# leptonBreakoutV4.net
KiCad netlist of a schematic drawn in EAGLE
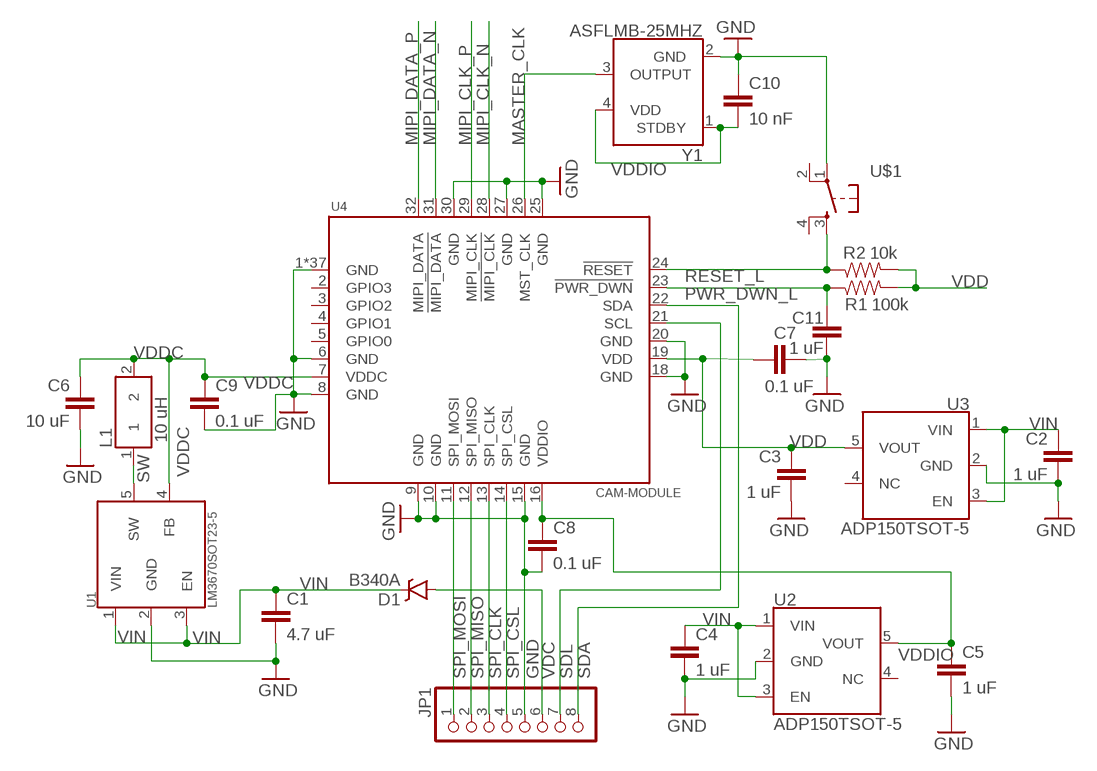
[diagram p0: schematic, sheet 1]

(export (version "E")
  (design (tool "Eeschema 10.0.6"))
  (components
    (comp (ref "C1")
      (value "4.7 uF")
      (footprint "eagle-import:0805")
      (libsource (lib "eagle-import") (part "CAP0805"))
    )
    (comp (ref "C2")
      (value "1 uF")
      (footprint "eagle-import:0805")
      (libsource (lib "eagle-import") (part "CAP0805"))
    )
    (comp (ref "C3")
      (value "1 uF")
      (footprint "eagle-import:0805")
      (libsource (lib "eagle-import") (part "CAP0805"))
    )
    (comp (ref "C4")
      (value "1 uF")
      (footprint "eagle-import:0805")
      (libsource (lib "eagle-import") (part "CAP0805"))
    )
    (comp (ref "C5")
      (value "1 uF")
      (footprint "eagle-import:0805")
      (libsource (lib "eagle-import") (part "CAP0805"))
    )
    (comp (ref "C6")
      (value "10 uF")
      (footprint "eagle-import:0805")
      (libsource (lib "eagle-import") (part "CAP0805"))
    )
    (comp (ref "C7")
      (value "0.1 uF")
      (footprint "eagle-import:0805")
      (libsource (lib "eagle-import") (part "CAP0805"))
    )
    (comp (ref "C8")
      (value "0.1 uF")
      (footprint "eagle-import:0805")
      (libsource (lib "eagle-import") (part "CAP0805"))
    )
    (comp (ref "C9")
      (value "0.1 uF")
      (footprint "eagle-import:0805")
      (libsource (lib "eagle-import") (part "CAP0805"))
    )
    (comp (ref "C10")
      (value "10 nF")
      (footprint "eagle-import:0805")
      (libsource (lib "eagle-import") (part "CAP0805"))
    )
    (comp (ref "C11")
      (value "1 uF")
      (footprint "eagle-import:0805")
      (libsource (lib "eagle-import") (part "CAP0805"))
    )
    (comp (ref "D1")
      (value "B340A")
      (footprint "eagle-import:SMA-DIODE")
      (libsource (lib "eagle-import") (part "DIODE-SCHOTTKY-B340A"))
    )
    (comp (ref "JP1")
      (value "PINHD-1X8/90")
      (footprint "eagle-import:1X08_90")
      (libsource (lib "eagle-import") (part "PINHD-1X8/90"))
    )
    (comp (ref "L1")
      (value "10 uH")
      (footprint "eagle-import:SMD-INDUCTOR")
      (libsource (lib "eagle-import") (part "SMD-INDUCTOR"))
    )
    (comp (ref "R1")
      (value "100k")
      (footprint "eagle-import:0805")
      (libsource (lib "eagle-import") (part "RESISTOR0805-RES"))
    )
    (comp (ref "R2")
      (value "10k")
      (footprint "eagle-import:0805")
      (libsource (lib "eagle-import") (part "RESISTOR0805-RES"))
    )
    (comp (ref "U$1")
      (value "TACTILE-SWITCH-7914G")
      (footprint "eagle-import:7914G")
      (libsource (lib "eagle-import") (part "TACTILE-SWITCH-7914G"))
    )
    (comp (ref "U1")
      (value "LM3670SOT23-5")
      (footprint "eagle-import:SOT23-5")
      (libsource (lib "eagle-import") (part "LM3670SOT23-5"))
    )
    (comp (ref "U2")
      (value "ADP150TSOT-5")
      (footprint "eagle-import:SOT23-5")
      (libsource (lib "eagle-import") (part "ADP150TSOT-5"))
    )
    (comp (ref "U3")
      (value "ADP150TSOT-5")
      (footprint "eagle-import:SOT23-5")
      (libsource (lib "eagle-import") (part "ADP150TSOT-5"))
    )
    (comp (ref "U4")
      (value "CAM-MODULE")
      (footprint "eagle-import:CAM-SOCKET")
      (libsource (lib "eagle-import") (part "CAM-MODULE"))
    )
    (comp (ref "Y1")
      (value "ASFLMB-25MHZ")
      (footprint "eagle-import:5X3.2-CRYSTAL-OSC")
      (libsource (lib "eagle-import") (part "ASFLMB-25MHZ"))
    )
  )
  (nets
    (net (code "1") (name "/MASTER_CLK") (class "Default")
      (node (ref "U4") (pin "26") (pinfunction "MST_CLK_26") (pintype "bidirectional"))
      (node (ref "Y1") (pin "3") (pinfunction "OUTPUT_3") (pintype "bidirectional"))
    )
    (net (code "2") (name "/MIPI_CLK_N") (class "Default")
      (node (ref "U4") (pin "28") (pinfunction "~{MIPI_CLK}_28") (pintype "bidirectional"))
    )
    (net (code "3") (name "/MIPI_CLK_P") (class "Default")
      (node (ref "U4") (pin "29") (pinfunction "MIPI_CLK_29") (pintype "bidirectional"))
    )
    (net (code "4") (name "/MIPI_DATA_N") (class "Default")
      (node (ref "U4") (pin "31") (pinfunction "~{MIPI_DATA}_31") (pintype "bidirectional"))
    )
    (net (code "5") (name "/MIPI_DATA_P") (class "Default")
      (node (ref "U4") (pin "32") (pinfunction "MIPI_DATA_32") (pintype "bidirectional"))
    )
    (net (code "6") (name "/PWR_DWN_L") (class "Default")
      (node (ref "C11") (pin "1") (pinfunction "1_1") (pintype "passive"))
      (node (ref "R1") (pin "1") (pinfunction "1_1") (pintype "passive"))
      (node (ref "U4") (pin "23") (pinfunction "~{PWR_DWN}_23") (pintype "bidirectional"))
    )
    (net (code "7") (name "/RESET_L") (class "Default")
      (node (ref "R2") (pin "1") (pinfunction "1_1") (pintype "passive"))
      (node (ref "U$1") (pin "3") (pinfunction "3_3") (pintype "passive"))
      (node (ref "U4") (pin "24") (pinfunction "~{RESET}_24") (pintype "bidirectional"))
    )
    (net (code "8") (name "/SDA") (class "Default")
      (node (ref "JP1") (pin "8") (pinfunction "8_8") (pintype "passive"))
      (node (ref "U4") (pin "22") (pinfunction "SDA_22") (pintype "bidirectional"))
    )
    (net (code "9") (name "/SDL") (class "Default")
      (node (ref "JP1") (pin "7") (pinfunction "7_7") (pintype "passive"))
      (node (ref "U4") (pin "21") (pinfunction "SCL_21") (pintype "bidirectional"))
    )
    (net (code "10") (name "/SPI_CLK") (class "Default")
      (node (ref "JP1") (pin "3") (pinfunction "3_3") (pintype "passive"))
      (node (ref "U4") (pin "13") (pinfunction "SPI_CLK_13") (pintype "bidirectional"))
    )
    (net (code "11") (name "/SPI_CSL") (class "Default")
      (node (ref "JP1") (pin "4") (pinfunction "4_4") (pintype "passive"))
      (node (ref "U4") (pin "14") (pinfunction "SPI_CSL_14") (pintype "bidirectional"))
    )
    (net (code "12") (name "/SPI_MISO") (class "Default")
      (node (ref "JP1") (pin "2") (pinfunction "2_2") (pintype "passive"))
      (node (ref "U4") (pin "12") (pinfunction "SPI_MISO_12") (pintype "bidirectional"))
    )
    (net (code "13") (name "/SPI_MOSI") (class "Default")
      (node (ref "JP1") (pin "1") (pinfunction "1_1") (pintype "passive"))
      (node (ref "U4") (pin "11") (pinfunction "SPI_MOSI_11") (pintype "bidirectional"))
    )
    (net (code "14") (name "/SW") (class "Default")
      (node (ref "L1") (pin "1") (pinfunction "1_1") (pintype "bidirectional"))
      (node (ref "U1") (pin "5") (pinfunction "SW_5") (pintype "power_in"))
    )
    (net (code "15") (name "/VDC") (class "Default")
      (node (ref "D1") (pin "A") (pinfunction "A_A") (pintype "passive"))
      (node (ref "JP1") (pin "6") (pinfunction "6_6") (pintype "passive"))
    )
    (net (code "16") (name "/VDD") (class "Default")
      (node (ref "C3") (pin "1") (pinfunction "1_1") (pintype "passive"))
      (node (ref "C7") (pin "1") (pinfunction "1_1") (pintype "passive"))
      (node (ref "R1") (pin "2") (pinfunction "2_2") (pintype "passive"))
      (node (ref "R2") (pin "2") (pinfunction "2_2") (pintype "passive"))
      (node (ref "U3") (pin "5") (pinfunction "VOUT_5") (pintype "power_in"))
      (node (ref "U4") (pin "19") (pinfunction "VDD_19") (pintype "power_in"))
    )
    (net (code "17") (name "/VDDC") (class "Default")
      (node (ref "C6") (pin "1") (pinfunction "1_1") (pintype "passive"))
      (node (ref "C9") (pin "1") (pinfunction "1_1") (pintype "passive"))
      (node (ref "L1") (pin "2") (pinfunction "2_2") (pintype "bidirectional"))
      (node (ref "U1") (pin "4") (pinfunction "FB_4") (pintype "bidirectional"))
      (node (ref "U4") (pin "7") (pinfunction "VDDC_7") (pintype "power_in"))
    )
    (net (code "18") (name "/VDDIO") (class "Default")
      (node (ref "C10") (pin "2") (pinfunction "2_2") (pintype "passive"))
      (node (ref "C5") (pin "1") (pinfunction "1_1") (pintype "passive"))
      (node (ref "C8") (pin "1") (pinfunction "1_1") (pintype "passive"))
      (node (ref "U2") (pin "5") (pinfunction "VOUT_5") (pintype "power_in"))
      (node (ref "U4") (pin "16") (pinfunction "VDDIO_16") (pintype "power_in"))
      (node (ref "Y1") (pin "1") (pinfunction "STDBY_1") (pintype "bidirectional"))
      (node (ref "Y1") (pin "4") (pinfunction "VDD_4") (pintype "power_in"))
    )
    (net (code "19") (name "/VIN") (class "Default")
      (node (ref "C1") (pin "1") (pinfunction "1_1") (pintype "passive"))
      (node (ref "C2") (pin "1") (pinfunction "1_1") (pintype "passive"))
      (node (ref "C4") (pin "1") (pinfunction "1_1") (pintype "passive"))
      (node (ref "D1") (pin "C") (pinfunction "C_C") (pintype "passive"))
      (node (ref "U1") (pin "1") (pinfunction "VIN_1") (pintype "power_in"))
      (node (ref "U1") (pin "3") (pinfunction "EN_3") (pintype "bidirectional"))
      (node (ref "U2") (pin "1") (pinfunction "VIN_1") (pintype "power_in"))
      (node (ref "U2") (pin "3") (pinfunction "EN_3") (pintype "bidirectional"))
      (node (ref "U3") (pin "1") (pinfunction "VIN_1") (pintype "power_in"))
      (node (ref "U3") (pin "3") (pinfunction "EN_3") (pintype "bidirectional"))
    )
    (net (code "20") (name "GND") (class "Default")
      (node (ref "C1") (pin "2") (pinfunction "2_2") (pintype "passive"))
      (node (ref "C10") (pin "1") (pinfunction "1_1") (pintype "passive"))
      (node (ref "C11") (pin "2") (pinfunction "2_2") (pintype "passive"))
      (node (ref "C2") (pin "2") (pinfunction "2_2") (pintype "passive"))
      (node (ref "C3") (pin "2") (pinfunction "2_2") (pintype "passive"))
      (node (ref "C4") (pin "2") (pinfunction "2_2") (pintype "passive"))
      (node (ref "C5") (pin "2") (pinfunction "2_2") (pintype "passive"))
      (node (ref "C6") (pin "2") (pinfunction "2_2") (pintype "passive"))
      (node (ref "C7") (pin "2") (pinfunction "2_2") (pintype "passive"))
      (node (ref "C8") (pin "2") (pinfunction "2_2") (pintype "passive"))
      (node (ref "C9") (pin "2") (pinfunction "2_2") (pintype "passive"))
      (node (ref "JP1") (pin "5") (pinfunction "5_5") (pintype "passive"))
      (node (ref "U$1") (pin "1") (pinfunction "1_1") (pintype "passive"))
      (node (ref "U1") (pin "2") (pinfunction "GND_2") (pintype "power_in"))
      (node (ref "U2") (pin "2") (pinfunction "GND_2") (pintype "power_in"))
      (node (ref "U3") (pin "2") (pinfunction "GND_2") (pintype "power_in"))
      (node (ref "U4") (pin "1") (pinfunction "GND_1") (pintype "power_in"))
      (node (ref "U4") (pin "10") (pinfunction "GND_10") (pintype "power_in"))
      (node (ref "U4") (pin "15") (pinfunction "GND_15") (pintype "power_in"))
      (node (ref "U4") (pin "18") (pinfunction "GND_18") (pintype "power_in"))
      (node (ref "U4") (pin "20") (pinfunction "GND_20") (pintype "power_in"))
      (node (ref "U4") (pin "25") (pinfunction "GND_25") (pintype "power_in"))
      (node (ref "U4") (pin "27") (pinfunction "GND_27") (pintype "power_in"))
      (node (ref "U4") (pin "30") (pinfunction "GND_30") (pintype "power_in"))
      (node (ref "U4") (pin "6") (pinfunction "GND_6") (pintype "power_in"))
      (node (ref "U4") (pin "8") (pinfunction "GND_8") (pintype "power_in"))
      (node (ref "U4") (pin "9") (pinfunction "GND_9") (pintype "power_in"))
      (node (ref "U4") (pin "P$1") (pinfunction "GND_P$1") (pintype "power_in"))
      (node (ref "U4") (pin "P$10") (pinfunction "GND_P$10") (pintype "power_in"))
      (node (ref "U4") (pin "P$11") (pinfunction "GND_P$11") (pintype "power_in"))
      (node (ref "U4") (pin "P$12") (pinfunction "GND_P$12") (pintype "power_in"))
      (node (ref "U4") (pin "P$13") (pinfunction "GND_P$13") (pintype "power_in"))
      (node (ref "U4") (pin "P$14") (pinfunction "GND_P$14") (pintype "power_in"))
      (node (ref "U4") (pin "P$15") (pinfunction "GND_P$15") (pintype "power_in"))
      (node (ref "U4") (pin "P$16") (pinfunction "GND_P$16") (pintype "power_in"))
      (node (ref "U4") (pin "P$17") (pinfunction "GND_P$17") (pintype "power_in"))
      (node (ref "U4") (pin "P$18") (pinfunction "GND_P$18") (pintype "power_in"))
      (node (ref "U4") (pin "P$19") (pinfunction "GND_P$19") (pintype "power_in"))
      (node (ref "U4") (pin "P$2") (pinfunction "GND_P$2") (pintype "power_in"))
      (node (ref "U4") (pin "P$20") (pinfunction "GND_P$20") (pintype "power_in"))
      (node (ref "U4") (pin "P$21") (pinfunction "GND_P$21") (pintype "power_in"))
      (node (ref "U4") (pin "P$22") (pinfunction "GND_P$22") (pintype "power_in"))
      (node (ref "U4") (pin "P$23") (pinfunction "GND_P$23") (pintype "power_in"))
      (node (ref "U4") (pin "P$24") (pinfunction "GND_P$24") (pintype "power_in"))
      (node (ref "U4") (pin "P$25") (pinfunction "GND_P$25") (pintype "power_in"))
      (node (ref "U4") (pin "P$26") (pinfunction "GND_P$26") (pintype "power_in"))
      (node (ref "U4") (pin "P$27") (pinfunction "GND_P$27") (pintype "power_in"))
      (node (ref "U4") (pin "P$28") (pinfunction "GND_P$28") (pintype "power_in"))
      (node (ref "U4") (pin "P$29") (pinfunction "GND_P$29") (pintype "power_in"))
      (node (ref "U4") (pin "P$3") (pinfunction "GND_P$3") (pintype "power_in"))
      (node (ref "U4") (pin "P$30") (pinfunction "GND_P$30") (pintype "power_in"))
      (node (ref "U4") (pin "P$31") (pinfunction "GND_P$31") (pintype "power_in"))
      (node (ref "U4") (pin "P$32") (pinfunction "GND_P$32") (pintype "power_in"))
      (node (ref "U4") (pin "P$33") (pinfunction "GND_P$33") (pintype "power_in"))
      (node (ref "U4") (pin "P$34") (pinfunction "GND_P$34") (pintype "power_in"))
      (node (ref "U4") (pin "P$35") (pinfunction "GND_P$35") (pintype "power_in"))
      (node (ref "U4") (pin "P$36") (pinfunction "GND_P$36") (pintype "power_in"))
      (node (ref "U4") (pin "P$4") (pinfunction "GND_P$4") (pintype "power_in"))
      (node (ref "U4") (pin "P$5") (pinfunction "GND_P$5") (pintype "power_in"))
      (node (ref "U4") (pin "P$6") (pinfunction "GND_P$6") (pintype "power_in"))
      (node (ref "U4") (pin "P$7") (pinfunction "GND_P$7") (pintype "power_in"))
      (node (ref "U4") (pin "P$8") (pinfunction "GND_P$8") (pintype "power_in"))
      (node (ref "U4") (pin "P$9") (pinfunction "GND_P$9") (pintype "power_in"))
      (node (ref "Y1") (pin "2") (pinfunction "GND_2") (pintype "power_in"))
    )
    (net (code "21") (name "unconnected-(U$1-Pad2)") (class "Default")
      (node (ref "U$1") (pin "2") (pinfunction "2_2") (pintype "passive"))
    )
    (net (code "22") (name "unconnected-(U$1-Pad4)") (class "Default")
      (node (ref "U$1") (pin "4") (pinfunction "4_4") (pintype "passive"))
    )
    (net (code "23") (name "unconnected-(U2-NC-Pad4)") (class "Default")
      (node (ref "U2") (pin "4") (pinfunction "NC_4") (pintype "bidirectional"))
    )
    (net (code "24") (name "unconnected-(U3-NC-Pad4)") (class "Default")
      (node (ref "U3") (pin "4") (pinfunction "NC_4") (pintype "bidirectional"))
    )
    (net (code "25") (name "unconnected-(U4-GPIO0-Pad5)") (class "Default")
      (node (ref "U4") (pin "5") (pinfunction "GPIO0_5") (pintype "bidirectional"))
    )
    (net (code "26") (name "unconnected-(U4-GPIO1-Pad4)") (class "Default")
      (node (ref "U4") (pin "4") (pinfunction "GPIO1_4") (pintype "bidirectional"))
    )
    (net (code "27") (name "unconnected-(U4-GPIO2-Pad3)") (class "Default")
      (node (ref "U4") (pin "3") (pinfunction "GPIO2_3") (pintype "bidirectional"))
    )
    (net (code "28") (name "unconnected-(U4-GPIO3-Pad2)") (class "Default")
      (node (ref "U4") (pin "2") (pinfunction "GPIO3_2") (pintype "bidirectional"))
    )
  )
)
